# cyberlamp.net
KiCad netlist of a schematic drawn in Altium Designer
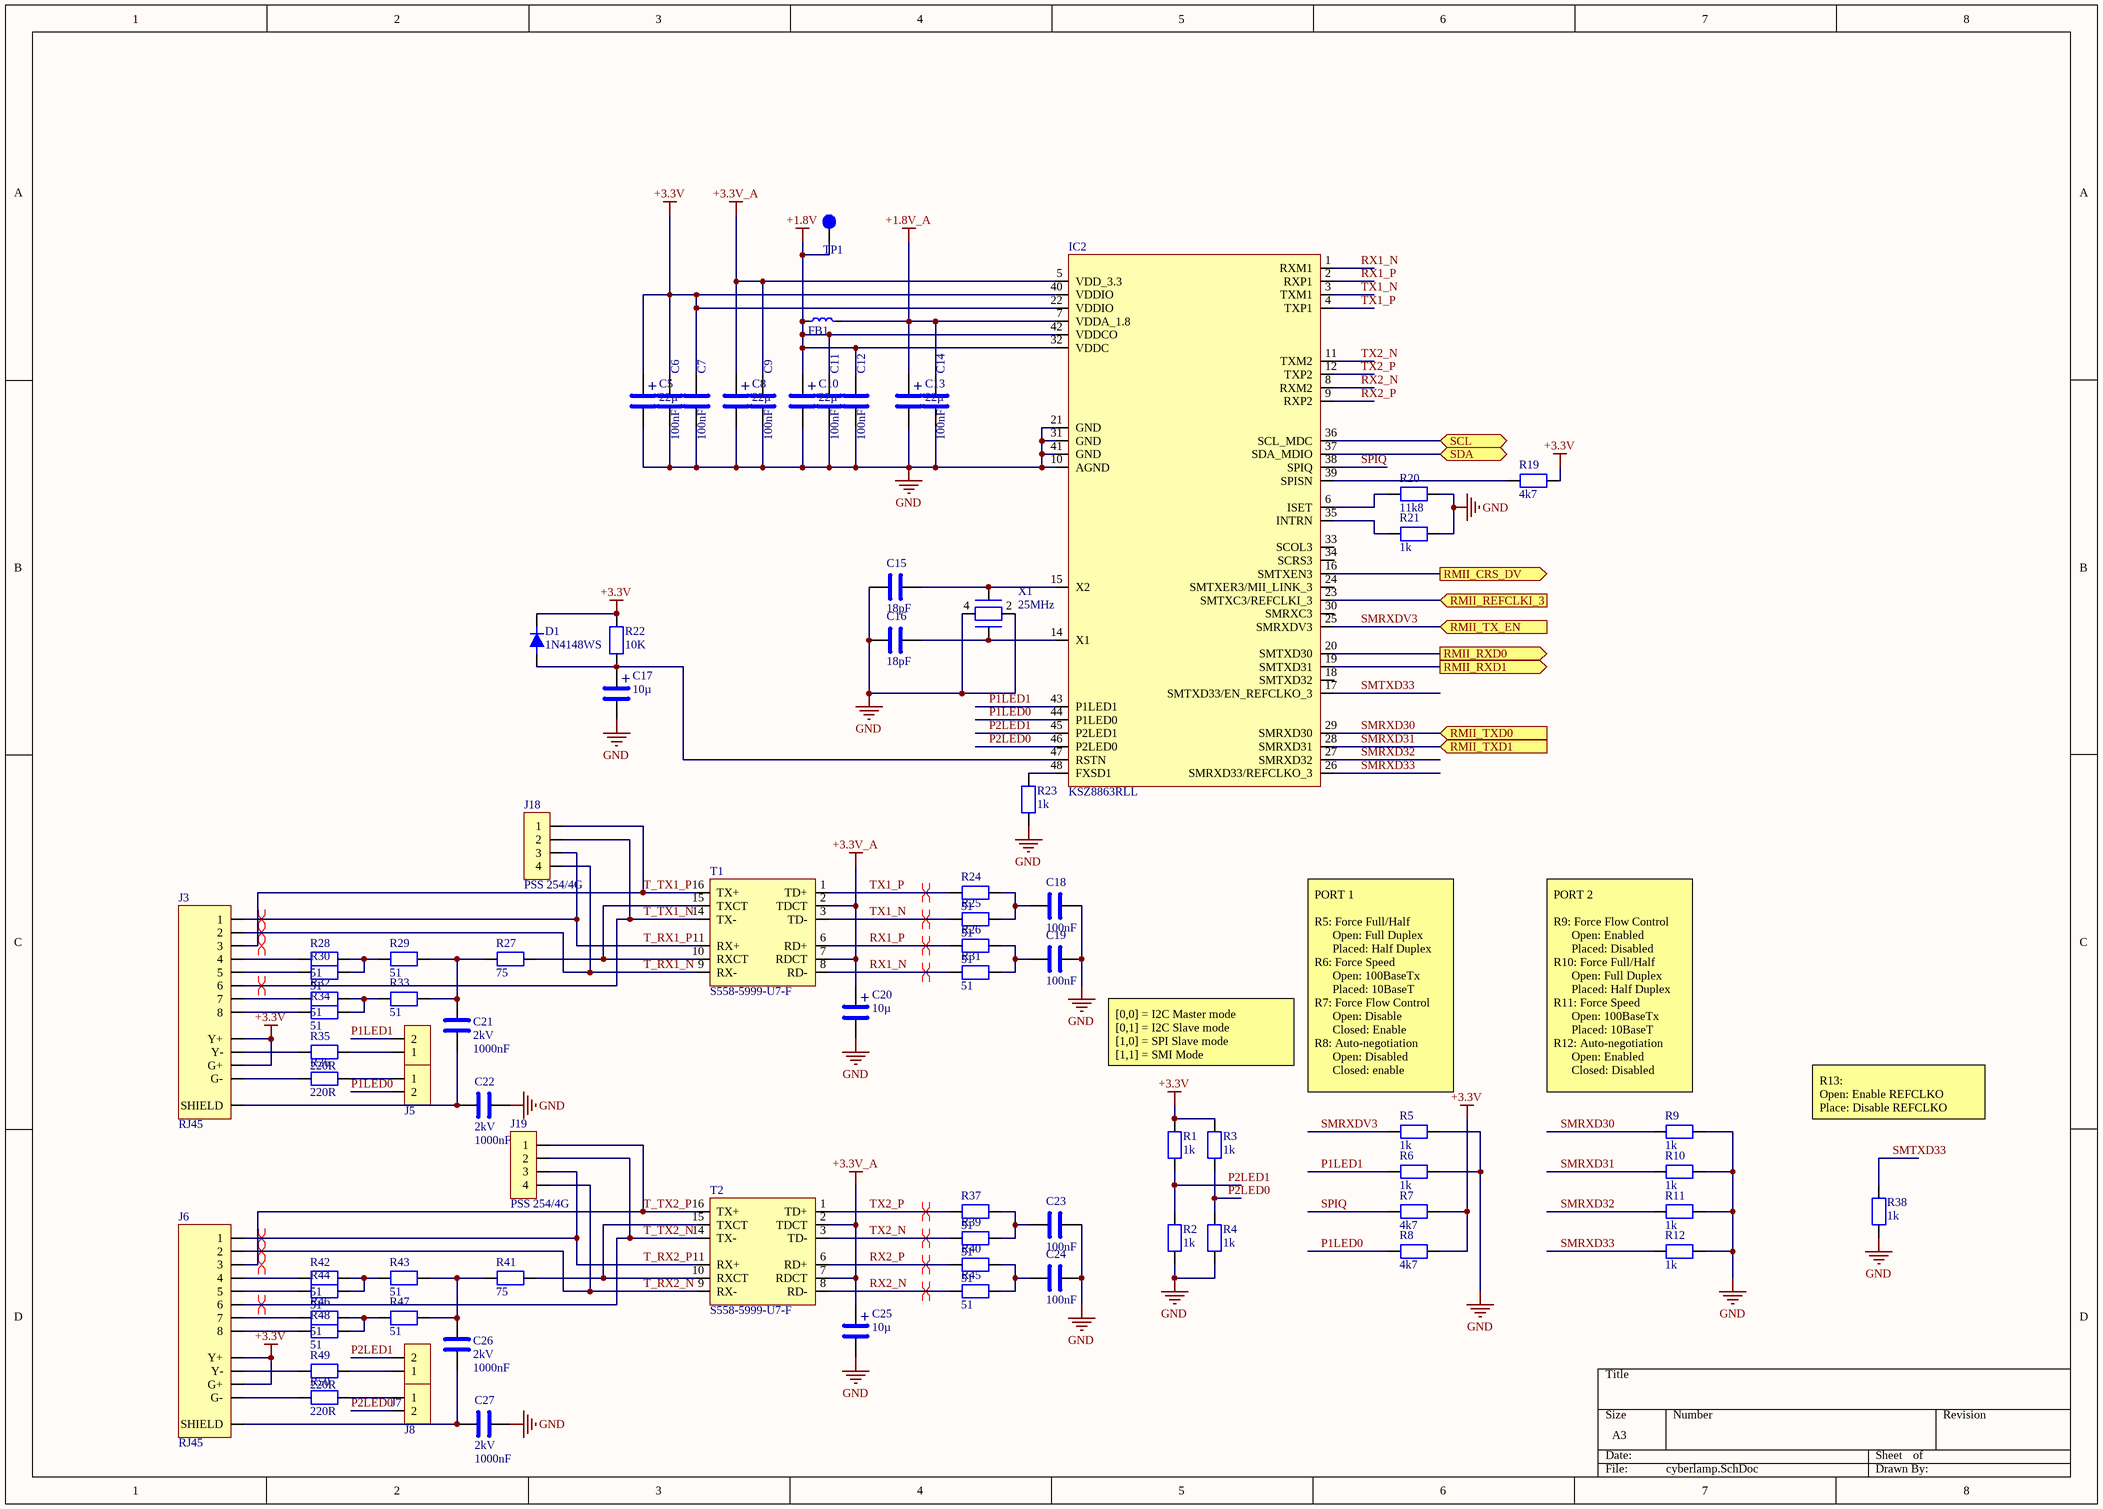
[diagram p0: cyberlamp.SchDoc]

(export (version "E")
  (design (tool "Eeschema 10.0.6"))
  (components
    (comp (ref "C5")
      (value "22µ")
      (footprint "WCAP-ASLU")
      (fields (field (name "VOLTAGE") "6.3V") (field (name "Comment") "Elko 22µF 6.3V WE"))
      (libsource (lib "elko") (part "Elko 22µF 6.3V WE"))
    )
    (comp (ref "C6")
      (value "100nF")
      (footprint "0603")
      (description "100nF 50V MLCC 0603")
      (fields (field (name "VOLTAGE") "50V"))
      (libsource (lib "capacitors") (part "100nF 50V MLCC 0603"))
    )
    (comp (ref "C7")
      (value "100nF")
      (footprint "0603")
      (description "100nF 50V MLCC 0603")
      (fields (field (name "VOLTAGE") "50V"))
      (libsource (lib "capacitors") (part "100nF 50V MLCC 0603"))
    )
    (comp (ref "C8")
      (value "22µ")
      (footprint "WCAP-ASLU")
      (fields (field (name "VOLTAGE") "6.3V") (field (name "Comment") "Elko 22µF 6.3V WE"))
      (libsource (lib "elko") (part "Elko 22µF 6.3V WE"))
    )
    (comp (ref "C9")
      (value "100nF")
      (footprint "0603")
      (description "100nF 50V MLCC 0603")
      (fields (field (name "VOLTAGE") "50V"))
      (libsource (lib "capacitors") (part "100nF 50V MLCC 0603"))
    )
    (comp (ref "C10")
      (value "22µ")
      (footprint "WCAP-ASLU")
      (fields (field (name "VOLTAGE") "6.3V") (field (name "Comment") "Elko 22µF 6.3V WE"))
      (libsource (lib "elko") (part "Elko 22µF 6.3V WE"))
    )
    (comp (ref "C11")
      (value "100nF")
      (footprint "0603")
      (description "100nF 50V MLCC 0603")
      (fields (field (name "VOLTAGE") "50V"))
      (libsource (lib "capacitors") (part "100nF 50V MLCC 0603"))
    )
    (comp (ref "C12")
      (value "100nF")
      (footprint "0603")
      (description "100nF 50V MLCC 0603")
      (fields (field (name "VOLTAGE") "50V"))
      (libsource (lib "capacitors") (part "100nF 50V MLCC 0603"))
    )
    (comp (ref "C13")
      (value "22µ")
      (footprint "WCAP-ASLU")
      (fields (field (name "VOLTAGE") "6.3V") (field (name "Comment") "Elko 22µF 6.3V WE"))
      (libsource (lib "elko") (part "Elko 22µF 6.3V WE"))
    )
    (comp (ref "C14")
      (value "100nF")
      (footprint "0603")
      (description "100nF 50V MLCC 0603")
      (fields (field (name "VOLTAGE") "50V"))
      (libsource (lib "capacitors") (part "100nF 50V MLCC 0603"))
    )
    (comp (ref "C15")
      (value "18pF")
      (footprint "0603")
      (description "18pF 50V MLCC 0603")
      (fields (field (name "VOLTAGE") "50V"))
      (libsource (lib "capacitors") (part "18pF 50V MLCC 0603"))
    )
    (comp (ref "C16")
      (value "18pF")
      (footprint "0603")
      (description "18pF 50V MLCC 0603")
      (fields (field (name "VOLTAGE") "50V"))
      (libsource (lib "capacitors") (part "18pF 50V MLCC 0603"))
    )
    (comp (ref "C17")
      (value "10µ")
      (footprint "Panasonic_b")
      (fields (field (name "VOLTAGE") "16V") (field (name "Comment") "Elko_10uF_16V_PanasonicB"))
      (libsource (lib "elkos") (part "Elko_10uF_16V_PanasonicB"))
    )
    (comp (ref "C18")
      (value "100nF")
      (footprint "0603")
      (description "100nF 50V MLCC 0603")
      (fields (field (name "VOLTAGE") "50V"))
      (libsource (lib "capacitors") (part "100nF 50V MLCC 0603"))
    )
    (comp (ref "C19")
      (value "100nF")
      (footprint "0603")
      (description "100nF 50V MLCC 0603")
      (fields (field (name "VOLTAGE") "50V"))
      (libsource (lib "capacitors") (part "100nF 50V MLCC 0603"))
    )
    (comp (ref "C20")
      (value "10µ")
      (footprint "Panasonic_b")
      (fields (field (name "VOLTAGE") "16V") (field (name "Comment") "Elko_10uF_16V_PanasonicB"))
      (libsource (lib "elkos") (part "Elko_10uF_16V_PanasonicB"))
    )
    (comp (ref "C21")
      (value "1000nF")
      (footprint "1206")
      (description "1000nF 2kV X7R 1206")
      (fields (field (name "VOLTAGE") "2kV") (field (name "Comment") "NP0"))
      (libsource (lib "capacitors") (part "1000nF 2kV X7R 1206"))
    )
    (comp (ref "C22")
      (value "1000nF")
      (footprint "1206")
      (description "1000nF 2kV X7R 1206")
      (fields (field (name "VOLTAGE") "2kV") (field (name "Comment") "NP0"))
      (libsource (lib "capacitors") (part "1000nF 2kV X7R 1206"))
    )
    (comp (ref "C23")
      (value "100nF")
      (footprint "0603")
      (description "100nF 50V MLCC 0603")
      (fields (field (name "VOLTAGE") "50V"))
      (libsource (lib "capacitors") (part "100nF 50V MLCC 0603"))
    )
    (comp (ref "C24")
      (value "100nF")
      (footprint "0603")
      (description "100nF 50V MLCC 0603")
      (fields (field (name "VOLTAGE") "50V"))
      (libsource (lib "capacitors") (part "100nF 50V MLCC 0603"))
    )
    (comp (ref "C25")
      (value "10µ")
      (footprint "Panasonic_b")
      (fields (field (name "VOLTAGE") "16V") (field (name "Comment") "Elko_10uF_16V_PanasonicB"))
      (libsource (lib "elkos") (part "Elko_10uF_16V_PanasonicB"))
    )
    (comp (ref "C26")
      (value "1000nF")
      (footprint "1206")
      (description "1000nF 2kV X7R 1206")
      (fields (field (name "VOLTAGE") "2kV") (field (name "Comment") "NP0"))
      (libsource (lib "capacitors") (part "1000nF 2kV X7R 1206"))
    )
    (comp (ref "C27")
      (value "1000nF")
      (footprint "1206")
      (description "1000nF 2kV X7R 1206")
      (fields (field (name "VOLTAGE") "2kV") (field (name "Comment") "NP0"))
      (libsource (lib "capacitors") (part "1000nF 2kV X7R 1206"))
    )
    (comp (ref "D1")
      (value "1N4148WS")
      (footprint "SOD323")
      (description "Small signal diode")
      (libsource (lib "diodes") (part "1N4148WS"))
    )
    (comp (ref "FB1")
      (value "HI1206N101R-10")
      (footprint "1206")
      (description "3A ferrit bead")
      (libsource (lib "inductors") (part "HI1206N101R-10"))
    )
    (comp (ref "IC2")
      (value "KSZ8863RLL")
      (footprint "LQFP48")
      (description "Dual port ethernet switch with RMII")
      (libsource (lib "misc") (part "KSZ8863RLL"))
    )
    (comp (ref "J3")
      (value "RJ45")
      (footprint "MTJ-88ARX1-FSM-PG-LH")
      (description "RJ45, shielded with LED")
      (libsource (lib "connectors_pc") (part "MTJ-88ARX1-FSM-PG-LH"))
    )
    (comp (ref "J4")
      (value "SL 1X2G 2,54")
      (footprint "SL_1x2 2.54mm")
      (description "Stiftleiste 2pol 2.54mm")
      (libsource (lib "connectors_sl") (part "SL 1X2G 2,54"))
    )
    (comp (ref "J5")
      (value "SL 1X2G 2,54")
      (footprint "SL_1x2 2.54mm")
      (description "Stiftleiste 2pol 2.54mm")
      (libsource (lib "") (part "SL 1X2G 2,54_1"))
    )
    (comp (ref "J6")
      (value "RJ45")
      (footprint "MTJ-88ARX1-FSM-PG-LH")
      (description "RJ45, shielded with LED")
      (libsource (lib "connectors_pc") (part "MTJ-88ARX1-FSM-PG-LH"))
    )
    (comp (ref "J7")
      (value "SL 1X2G 2,54")
      (footprint "SL_1x2 2.54mm")
      (description "Stiftleiste 2pol 2.54mm")
      (libsource (lib "connectors_sl") (part "SL 1X2G 2,54"))
    )
    (comp (ref "J8")
      (value "SL 1X2G 2,54")
      (footprint "SL_1x2 2.54mm")
      (description "Stiftleiste 2pol 2.54mm")
      (libsource (lib "") (part "SL 1X2G 2,54_1"))
    )
    (comp (ref "J18")
      (value "PSS 254/4G")
      (footprint "PSS 4pol")
      (description "PSS 4pol wire-to-board-connector")
      (libsource (lib "connectors_pss") (part "PSS 254/4G"))
    )
    (comp (ref "J19")
      (value "PSS 254/4G")
      (footprint "PSS 4pol")
      (description "PSS 4pol wire-to-board-connector")
      (libsource (lib "connectors_pss") (part "PSS 254/4G"))
    )
    (comp (ref "R1")
      (value "1k")
      (footprint "res0603")
      (description "1k 100mW 0603")
      (fields (field (name "TOLERANCE") "1%"))
      (libsource (lib "resistors0603") (part "1k 100mW 0603"))
    )
    (comp (ref "R2")
      (value "1k")
      (footprint "res0603")
      (description "1k 100mW 0603")
      (fields (field (name "TOLERANCE") "1%"))
      (libsource (lib "resistors0603") (part "1k 100mW 0603"))
    )
    (comp (ref "R3")
      (value "1k")
      (footprint "res0603")
      (description "1k 100mW 0603")
      (fields (field (name "TOLERANCE") "1%"))
      (libsource (lib "resistors0603") (part "1k 100mW 0603"))
    )
    (comp (ref "R4")
      (value "1k")
      (footprint "res0603")
      (description "1k 100mW 0603")
      (fields (field (name "TOLERANCE") "1%"))
      (libsource (lib "resistors0603") (part "1k 100mW 0603"))
    )
    (comp (ref "R5")
      (value "1k")
      (footprint "res0603")
      (description "1k 100mW 0603")
      (fields (field (name "TOLERANCE") "1%"))
      (libsource (lib "resistors0603") (part "1k 100mW 0603"))
    )
    (comp (ref "R6")
      (value "1k")
      (footprint "res0603")
      (description "1k 100mW 0603")
      (fields (field (name "TOLERANCE") "1%"))
      (libsource (lib "resistors0603") (part "1k 100mW 0603"))
    )
    (comp (ref "R7")
      (value "4k7")
      (footprint "res0603")
      (description "4k7 100mW 0603")
      (libsource (lib "resistors") (part "4k7 100mW 0603"))
    )
    (comp (ref "R8")
      (value "4k7")
      (footprint "res0603")
      (description "4k7 100mW 0603")
      (libsource (lib "resistors") (part "4k7 100mW 0603"))
    )
    (comp (ref "R9")
      (value "1k")
      (footprint "res0603")
      (description "1k 100mW 0603")
      (fields (field (name "TOLERANCE") "1%"))
      (libsource (lib "resistors0603") (part "1k 100mW 0603"))
    )
    (comp (ref "R10")
      (value "1k")
      (footprint "res0603")
      (description "1k 100mW 0603")
      (fields (field (name "TOLERANCE") "1%"))
      (libsource (lib "resistors0603") (part "1k 100mW 0603"))
    )
    (comp (ref "R11")
      (value "1k")
      (footprint "res0603")
      (description "1k 100mW 0603")
      (fields (field (name "TOLERANCE") "1%"))
      (libsource (lib "resistors0603") (part "1k 100mW 0603"))
    )
    (comp (ref "R12")
      (value "1k")
      (footprint "res0603")
      (description "1k 100mW 0603")
      (fields (field (name "TOLERANCE") "1%"))
      (libsource (lib "resistors0603") (part "1k 100mW 0603"))
    )
    (comp (ref "R19")
      (value "4k7")
      (footprint "res0603")
      (description "4k7 100mW 0603")
      (libsource (lib "resistors") (part "4k7 100mW 0603"))
    )
    (comp (ref "R20")
      (value "11k8")
      (footprint "res0603")
      (description "11k8 100mW 0603")
      (fields (field (name "TOLERANCE") "1%"))
      (libsource (lib "resistors0603") (part "11k8 100mW 0603"))
    )
    (comp (ref "R21")
      (value "1k")
      (footprint "res0603")
      (description "1k 100mW 0603")
      (fields (field (name "TOLERANCE") "1%"))
      (libsource (lib "resistors0603") (part "1k 100mW 0603"))
    )
    (comp (ref "R22")
      (value "10K")
      (footprint "res0603")
      (description "10K 100mW 0603")
      (fields (field (name "TOLERANCE") "1%"))
      (libsource (lib "resistors") (part "10K 100mW 0603"))
    )
    (comp (ref "R23")
      (value "1k")
      (footprint "res0603")
      (description "1k 100mW 0603")
      (fields (field (name "TOLERANCE") "1%"))
      (libsource (lib "resistors0603") (part "1k 100mW 0603"))
    )
    (comp (ref "R24")
      (value "51")
      (footprint "res0603")
      (description "51 100mW 0603")
      (fields (field (name "TOLERANCE") "5%") (field (name "Comment") "51R 100mW 0603"))
      (libsource (lib "resistors0603") (part "51R 100mW 0603"))
    )
    (comp (ref "R25")
      (value "51")
      (footprint "res0603")
      (description "51 100mW 0603")
      (fields (field (name "TOLERANCE") "5%") (field (name "Comment") "51R 100mW 0603"))
      (libsource (lib "resistors0603") (part "51R 100mW 0603"))
    )
    (comp (ref "R26")
      (value "51")
      (footprint "res0603")
      (description "51 100mW 0603")
      (fields (field (name "TOLERANCE") "5%") (field (name "Comment") "51R 100mW 0603"))
      (libsource (lib "resistors0603") (part "51R 100mW 0603"))
    )
    (comp (ref "R27")
      (value "75")
      (footprint "res0603")
      (description "75 100mW 0603")
      (fields (field (name "TOLERANCE") "1%") (field (name "Comment") "75R 100mW 0603"))
      (libsource (lib "resistors0603") (part "75R 100mW 0603"))
    )
    (comp (ref "R28")
      (value "51")
      (footprint "res0603")
      (description "51 100mW 0603")
      (fields (field (name "TOLERANCE") "5%") (field (name "Comment") "51R 100mW 0603"))
      (libsource (lib "resistors0603") (part "51R 100mW 0603"))
    )
    (comp (ref "R29")
      (value "51")
      (footprint "res0603")
      (description "51 100mW 0603")
      (fields (field (name "TOLERANCE") "5%") (field (name "Comment") "51R 100mW 0603"))
      (libsource (lib "resistors0603") (part "51R 100mW 0603"))
    )
    (comp (ref "R30")
      (value "51")
      (footprint "res0603")
      (description "51 100mW 0603")
      (fields (field (name "TOLERANCE") "5%") (field (name "Comment") "51R 100mW 0603"))
      (libsource (lib "resistors0603") (part "51R 100mW 0603"))
    )
    (comp (ref "R31")
      (value "51")
      (footprint "res0603")
      (description "51 100mW 0603")
      (fields (field (name "TOLERANCE") "5%") (field (name "Comment") "51R 100mW 0603"))
      (libsource (lib "resistors0603") (part "51R 100mW 0603"))
    )
    (comp (ref "R32")
      (value "51")
      (footprint "res0603")
      (description "51 100mW 0603")
      (fields (field (name "TOLERANCE") "5%") (field (name "Comment") "51R 100mW 0603"))
      (libsource (lib "resistors0603") (part "51R 100mW 0603"))
    )
    (comp (ref "R33")
      (value "51")
      (footprint "res0603")
      (description "51 100mW 0603")
      (fields (field (name "TOLERANCE") "5%") (field (name "Comment") "51R 100mW 0603"))
      (libsource (lib "resistors0603") (part "51R 100mW 0603"))
    )
    (comp (ref "R34")
      (value "51")
      (footprint "res0603")
      (description "51 100mW 0603")
      (fields (field (name "TOLERANCE") "5%") (field (name "Comment") "51R 100mW 0603"))
      (libsource (lib "resistors0603") (part "51R 100mW 0603"))
    )
    (comp (ref "R35")
      (value "220R")
      (footprint "res0603")
      (description "220R 100mW 0603")
      (fields (field (name "TOLERANCE") "1%"))
      (libsource (lib "resistors0603") (part "220R 100mW 0603"))
    )
    (comp (ref "R36")
      (value "220R")
      (footprint "res0603")
      (description "220R 100mW 0603")
      (fields (field (name "TOLERANCE") "1%"))
      (libsource (lib "resistors0603") (part "220R 100mW 0603"))
    )
    (comp (ref "R37")
      (value "51")
      (footprint "res0603")
      (description "51 100mW 0603")
      (fields (field (name "TOLERANCE") "5%") (field (name "Comment") "51R 100mW 0603"))
      (libsource (lib "resistors0603") (part "51R 100mW 0603"))
    )
    (comp (ref "R38")
      (value "1k")
      (footprint "res0603")
      (description "1k 100mW 0603")
      (fields (field (name "TOLERANCE") "1%"))
      (libsource (lib "resistors0603") (part "1k 100mW 0603"))
    )
    (comp (ref "R39")
      (value "51")
      (footprint "res0603")
      (description "51 100mW 0603")
      (fields (field (name "TOLERANCE") "5%") (field (name "Comment") "51R 100mW 0603"))
      (libsource (lib "resistors0603") (part "51R 100mW 0603"))
    )
    (comp (ref "R40")
      (value "51")
      (footprint "res0603")
      (description "51 100mW 0603")
      (fields (field (name "TOLERANCE") "5%") (field (name "Comment") "51R 100mW 0603"))
      (libsource (lib "resistors0603") (part "51R 100mW 0603"))
    )
    (comp (ref "R41")
      (value "75")
      (footprint "res0603")
      (description "75 100mW 0603")
      (fields (field (name "TOLERANCE") "1%") (field (name "Comment") "75R 100mW 0603"))
      (libsource (lib "resistors0603") (part "75R 100mW 0603"))
    )
    (comp (ref "R42")
      (value "51")
      (footprint "res0603")
      (description "51 100mW 0603")
      (fields (field (name "TOLERANCE") "5%") (field (name "Comment") "51R 100mW 0603"))
      (libsource (lib "resistors0603") (part "51R 100mW 0603"))
    )
    (comp (ref "R43")
      (value "51")
      (footprint "res0603")
      (description "51 100mW 0603")
      (fields (field (name "TOLERANCE") "5%") (field (name "Comment") "51R 100mW 0603"))
      (libsource (lib "resistors0603") (part "51R 100mW 0603"))
    )
    (comp (ref "R44")
      (value "51")
      (footprint "res0603")
      (description "51 100mW 0603")
      (fields (field (name "TOLERANCE") "5%") (field (name "Comment") "51R 100mW 0603"))
      (libsource (lib "resistors0603") (part "51R 100mW 0603"))
    )
    (comp (ref "R45")
      (value "51")
      (footprint "res0603")
      (description "51 100mW 0603")
      (fields (field (name "TOLERANCE") "5%") (field (name "Comment") "51R 100mW 0603"))
      (libsource (lib "resistors0603") (part "51R 100mW 0603"))
    )
    (comp (ref "R46")
      (value "51")
      (footprint "res0603")
      (description "51 100mW 0603")
      (fields (field (name "TOLERANCE") "5%") (field (name "Comment") "51R 100mW 0603"))
      (libsource (lib "resistors0603") (part "51R 100mW 0603"))
    )
    (comp (ref "R47")
      (value "51")
      (footprint "res0603")
      (description "51 100mW 0603")
      (fields (field (name "TOLERANCE") "5%") (field (name "Comment") "51R 100mW 0603"))
      (libsource (lib "resistors0603") (part "51R 100mW 0603"))
    )
    (comp (ref "R48")
      (value "51")
      (footprint "res0603")
      (description "51 100mW 0603")
      (fields (field (name "TOLERANCE") "5%") (field (name "Comment") "51R 100mW 0603"))
      (libsource (lib "resistors0603") (part "51R 100mW 0603"))
    )
    (comp (ref "R49")
      (value "220R")
      (footprint "res0603")
      (description "220R 100mW 0603")
      (fields (field (name "TOLERANCE") "1%"))
      (libsource (lib "resistors0603") (part "220R 100mW 0603"))
    )
    (comp (ref "R50")
      (value "220R")
      (footprint "res0603")
      (description "220R 100mW 0603")
      (fields (field (name "TOLERANCE") "1%"))
      (libsource (lib "resistors0603") (part "220R 100mW 0603"))
    )
    (comp (ref "T1")
      (value "S558-5999-U7-F")
      (footprint "S558-5999-U7-F")
      (description "Ethernet transformer")
      (libsource (lib "inductors2") (part "S558-5999-U7-F"))
    )
    (comp (ref "T2")
      (value "S558-5999-U7-F")
      (footprint "S558-5999-U7-F")
      (description "Ethernet transformer")
      (libsource (lib "inductors2") (part "S558-5999-U7-F"))
    )
    (comp (ref "TP1") (value "testpoint") (footprint "testpoint") (libsource (lib "misc") (part "testpoint")))
    (comp (ref "X1")
      (value "25MHz")
      (footprint "ABM8")
      (description "ABM8 25MHz crystal")
      (libsource (lib "crystals") (part "ABM8-25.000MHZ-B2-T"))
    )
  )
  (nets
    (net (code "1") (name "+1.8V") (class "Default")
      (node (ref "C10") (pin "+") (pinfunction "+_+") (pintype "passive"))
      (node (ref "C11") (pin "1") (pinfunction "1_1") (pintype "passive"))
      (node (ref "C12") (pin "1") (pinfunction "1_1") (pintype "passive"))
      (node (ref "FB1") (pin "1") (pinfunction "1_1") (pintype "passive"))
      (node (ref "IC2") (pin "32") (pinfunction "VDDC_32") (pintype "passive"))
      (node (ref "IC2") (pin "42") (pinfunction "VDDCO_42") (pintype "passive"))
      (node (ref "TP1") (pin "1") (pinfunction "1_1") (pintype "passive"))
    )
    (net (code "2") (name "+1.8V_A") (class "Default")
      (node (ref "C13") (pin "+") (pinfunction "+_+") (pintype "passive"))
      (node (ref "C14") (pin "1") (pinfunction "1_1") (pintype "passive"))
      (node (ref "FB1") (pin "2") (pinfunction "2_2") (pintype "passive"))
      (node (ref "IC2") (pin "7") (pinfunction "VDDA_1.8_7") (pintype "passive"))
    )
    (net (code "3") (name "+3.3V") (class "Default")
      (node (ref "C5") (pin "+") (pinfunction "+_+") (pintype "passive"))
      (node (ref "C6") (pin "1") (pinfunction "1_1") (pintype "passive"))
      (node (ref "C7") (pin "1") (pinfunction "1_1") (pintype "passive"))
      (node (ref "D1") (pin "1") (pinfunction "1_1") (pintype "passive"))
      (node (ref "IC2") (pin "22") (pinfunction "VDDIO_22") (pintype "passive"))
      (node (ref "IC2") (pin "40") (pinfunction "VDDIO_40") (pintype "passive"))
      (node (ref "J3") (pin "10") (pinfunction "Y+_10") (pintype "passive"))
      (node (ref "J3") (pin "12") (pinfunction "G+_12") (pintype "passive"))
      (node (ref "J6") (pin "10") (pinfunction "Y+_10") (pintype "passive"))
      (node (ref "J6") (pin "12") (pinfunction "G+_12") (pintype "passive"))
      (node (ref "R1") (pin "2") (pinfunction "2_2") (pintype "passive"))
      (node (ref "R19") (pin "1") (pinfunction "1_1") (pintype "passive"))
      (node (ref "R22") (pin "2") (pinfunction "2_2") (pintype "passive"))
      (node (ref "R3") (pin "2") (pinfunction "2_2") (pintype "passive"))
      (node (ref "R7") (pin "1") (pinfunction "1_1") (pintype "passive"))
      (node (ref "R8") (pin "1") (pinfunction "1_1") (pintype "passive"))
    )
    (net (code "4") (name "+3.3V_A") (class "Default")
      (node (ref "C20") (pin "+") (pinfunction "+_+") (pintype "passive"))
      (node (ref "C25") (pin "+") (pinfunction "+_+") (pintype "passive"))
      (node (ref "C8") (pin "+") (pinfunction "+_+") (pintype "passive"))
      (node (ref "C9") (pin "1") (pinfunction "1_1") (pintype "passive"))
      (node (ref "IC2") (pin "5") (pinfunction "VDD_3.3_5") (pintype "passive"))
      (node (ref "T1") (pin "2") (pinfunction "TDCT_2") (pintype "passive"))
      (node (ref "T1") (pin "7") (pinfunction "RDCT_7") (pintype "passive"))
      (node (ref "T2") (pin "2") (pinfunction "TDCT_2") (pintype "passive"))
      (node (ref "T2") (pin "7") (pinfunction "RDCT_7") (pintype "passive"))
    )
    (net (code "5") (name "/P1LED0") (class "Default")
      (node (ref "IC2") (pin "44") (pinfunction "P1LED0_44") (pintype "passive"))
      (node (ref "J5") (pin "2") (pinfunction "2_2") (pintype "passive"))
      (node (ref "R8") (pin "2") (pinfunction "2_2") (pintype "passive"))
    )
    (net (code "6") (name "/P1LED1") (class "Default")
      (node (ref "IC2") (pin "43") (pinfunction "P1LED1_43") (pintype "passive"))
      (node (ref "J4") (pin "2") (pinfunction "2_2") (pintype "passive"))
      (node (ref "R6") (pin "2") (pinfunction "2_2") (pintype "passive"))
    )
    (net (code "7") (name "/P2LED0") (class "Default")
      (node (ref "IC2") (pin "46") (pinfunction "P2LED0_46") (pintype "passive"))
      (node (ref "J8") (pin "2") (pinfunction "2_2") (pintype "passive"))
      (node (ref "R3") (pin "1") (pinfunction "1_1") (pintype "passive"))
      (node (ref "R4") (pin "2") (pinfunction "2_2") (pintype "passive"))
    )
    (net (code "8") (name "/P2LED1") (class "Default")
      (node (ref "IC2") (pin "45") (pinfunction "P2LED1_45") (pintype "passive"))
      (node (ref "J7") (pin "2") (pinfunction "2_2") (pintype "passive"))
      (node (ref "R1") (pin "1") (pinfunction "1_1") (pintype "passive"))
      (node (ref "R2") (pin "2") (pinfunction "2_2") (pintype "passive"))
    )
    (net (code "9") (name "/RMII_CRS_DV") (class "Default")
      (node (ref "IC2") (pin "16") (pinfunction "SMTXEN3_16") (pintype "passive"))
    )
    (net (code "10") (name "/RMII_REFCLKI_3") (class "Default")
      (node (ref "IC2") (pin "23") (pinfunction "SMTXC3/REFCLKI_3_23") (pintype "passive"))
    )
    (net (code "11") (name "/RMII_RXD0") (class "Default")
      (node (ref "IC2") (pin "20") (pinfunction "SMTXD30_20") (pintype "passive"))
    )
    (net (code "12") (name "/RMII_RXD1") (class "Default")
      (node (ref "IC2") (pin "19") (pinfunction "SMTXD31_19") (pintype "passive"))
    )
    (net (code "13") (name "/RX1_N") (class "Default")
      (node (ref "IC2") (pin "1") (pinfunction "RXM1_1") (pintype "passive"))
      (node (ref "R31") (pin "2") (pinfunction "2_2") (pintype "passive"))
      (node (ref "T1") (pin "8") (pinfunction "RD-_8") (pintype "passive"))
    )
    (net (code "14") (name "/RX1_P") (class "Default")
      (node (ref "IC2") (pin "2") (pinfunction "RXP1_2") (pintype "passive"))
      (node (ref "R26") (pin "2") (pinfunction "2_2") (pintype "passive"))
      (node (ref "T1") (pin "6") (pinfunction "RD+_6") (pintype "passive"))
    )
    (net (code "15") (name "/RX2_N") (class "Default")
      (node (ref "IC2") (pin "8") (pinfunction "RXM2_8") (pintype "passive"))
      (node (ref "R45") (pin "2") (pinfunction "2_2") (pintype "passive"))
      (node (ref "T2") (pin "8") (pinfunction "RD-_8") (pintype "passive"))
    )
    (net (code "16") (name "/RX2_P") (class "Default")
      (node (ref "IC2") (pin "9") (pinfunction "RXP2_9") (pintype "passive"))
      (node (ref "R40") (pin "2") (pinfunction "2_2") (pintype "passive"))
      (node (ref "T2") (pin "6") (pinfunction "RD+_6") (pintype "passive"))
    )
    (net (code "17") (name "/SCL") (class "Default")
      (node (ref "IC2") (pin "36") (pinfunction "SCL_MDC_36") (pintype "passive"))
    )
    (net (code "18") (name "/SDA") (class "Default")
      (node (ref "IC2") (pin "37") (pinfunction "SDA_MDIO_37") (pintype "passive"))
    )
    (net (code "19") (name "/SMRXD30") (class "Default")
      (node (ref "IC2") (pin "29") (pinfunction "SMRXD30_29") (pintype "passive"))
      (node (ref "R9") (pin "2") (pinfunction "2_2") (pintype "passive"))
    )
    (net (code "20") (name "/SMRXD31") (class "Default")
      (node (ref "IC2") (pin "28") (pinfunction "SMRXD31_28") (pintype "passive"))
      (node (ref "R10") (pin "2") (pinfunction "2_2") (pintype "passive"))
    )
    (net (code "21") (name "/SMRXD32") (class "Default")
      (node (ref "IC2") (pin "27") (pinfunction "SMRXD32_27") (pintype "passive"))
      (node (ref "R11") (pin "2") (pinfunction "2_2") (pintype "passive"))
    )
    (net (code "22") (name "/SMRXD33") (class "Default")
      (node (ref "IC2") (pin "26") (pinfunction "SMRXD33/REFCLKO_3_26") (pintype "passive"))
      (node (ref "R12") (pin "2") (pinfunction "2_2") (pintype "passive"))
    )
    (net (code "23") (name "/SMRXDV3") (class "Default")
      (node (ref "IC2") (pin "25") (pinfunction "SMRXDV3_25") (pintype "passive"))
      (node (ref "R5") (pin "2") (pinfunction "2_2") (pintype "passive"))
    )
    (net (code "24") (name "/SMTXD33") (class "Default")
      (node (ref "IC2") (pin "17") (pinfunction "SMTXD33/EN_REFCLKO_3_17") (pintype "passive"))
      (node (ref "R38") (pin "1") (pinfunction "1_1") (pintype "passive"))
    )
    (net (code "25") (name "/SPIQ") (class "Default")
      (node (ref "IC2") (pin "38") (pinfunction "SPIQ_38") (pintype "passive"))
      (node (ref "R7") (pin "2") (pinfunction "2_2") (pintype "passive"))
    )
    (net (code "26") (name "/TX1_N") (class "Default")
      (node (ref "IC2") (pin "3") (pinfunction "TXM1_3") (pintype "passive"))
      (node (ref "R25") (pin "2") (pinfunction "2_2") (pintype "passive"))
      (node (ref "T1") (pin "3") (pinfunction "TD-_3") (pintype "passive"))
    )
    (net (code "27") (name "/TX1_P") (class "Default")
      (node (ref "IC2") (pin "4") (pinfunction "TXP1_4") (pintype "passive"))
      (node (ref "R24") (pin "2") (pinfunction "2_2") (pintype "passive"))
      (node (ref "T1") (pin "1") (pinfunction "TD+_1") (pintype "passive"))
    )
    (net (code "28") (name "/TX2_N") (class "Default")
      (node (ref "IC2") (pin "11") (pinfunction "TXM2_11") (pintype "passive"))
      (node (ref "R39") (pin "2") (pinfunction "2_2") (pintype "passive"))
      (node (ref "T2") (pin "3") (pinfunction "TD-_3") (pintype "passive"))
    )
    (net (code "29") (name "/TX2_P") (class "Default")
      (node (ref "IC2") (pin "12") (pinfunction "TXP2_12") (pintype "passive"))
      (node (ref "R37") (pin "2") (pinfunction "2_2") (pintype "passive"))
      (node (ref "T2") (pin "1") (pinfunction "TD+_1") (pintype "passive"))
    )
    (net (code "30") (name "/T_RX1_N") (class "Default")
      (node (ref "J18") (pin "4") (pinfunction "4_4") (pintype "passive"))
      (node (ref "J3") (pin "2") (pinfunction "2_2") (pintype "passive"))
      (node (ref "T1") (pin "9") (pinfunction "RX-_9") (pintype "passive"))
    )
    (net (code "31") (name "/T_RX1_P") (class "Default")
      (node (ref "J18") (pin "3") (pinfunction "3_3") (pintype "passive"))
      (node (ref "J3") (pin "1") (pinfunction "1_1") (pintype "passive"))
      (node (ref "T1") (pin "11") (pinfunction "RX+_11") (pintype "passive"))
    )
    (net (code "32") (name "/T_RX2_N") (class "Default")
      (node (ref "J19") (pin "4") (pinfunction "4_4") (pintype "passive"))
      (node (ref "J6") (pin "2") (pinfunction "2_2") (pintype "passive"))
      (node (ref "T2") (pin "9") (pinfunction "RX-_9") (pintype "passive"))
    )
    (net (code "33") (name "/T_RX2_P") (class "Default")
      (node (ref "J19") (pin "3") (pinfunction "3_3") (pintype "passive"))
      (node (ref "J6") (pin "1") (pinfunction "1_1") (pintype "passive"))
      (node (ref "T2") (pin "11") (pinfunction "RX+_11") (pintype "passive"))
    )
    (net (code "34") (name "/T_TX1_N") (class "Default")
      (node (ref "J18") (pin "2") (pinfunction "2_2") (pintype "passive"))
      (node (ref "J3") (pin "6") (pinfunction "6_6") (pintype "passive"))
      (node (ref "T1") (pin "14") (pinfunction "TX-_14") (pintype "passive"))
    )
    (net (code "35") (name "/T_TX1_P") (class "Default")
      (node (ref "J18") (pin "1") (pinfunction "1_1") (pintype "passive"))
      (node (ref "J3") (pin "3") (pinfunction "3_3") (pintype "passive"))
      (node (ref "T1") (pin "16") (pinfunction "TX+_16") (pintype "passive"))
    )
    (net (code "36") (name "/T_TX2_N") (class "Default")
      (node (ref "J19") (pin "2") (pinfunction "2_2") (pintype "passive"))
      (node (ref "J6") (pin "6") (pinfunction "6_6") (pintype "passive"))
      (node (ref "T2") (pin "14") (pinfunction "TX-_14") (pintype "passive"))
    )
    (net (code "37") (name "/T_TX2_P") (class "Default")
      (node (ref "J19") (pin "1") (pinfunction "1_1") (pintype "passive"))
      (node (ref "J6") (pin "3") (pinfunction "3_3") (pintype "passive"))
      (node (ref "T2") (pin "16") (pinfunction "TX+_16") (pintype "passive"))
    )
    (net (code "38") (name "GND") (class "Default")
      (node (ref "C10") (pin "-") (pinfunction "-_-") (pintype "passive"))
      (node (ref "C11") (pin "2") (pinfunction "2_2") (pintype "passive"))
      (node (ref "C12") (pin "2") (pinfunction "2_2") (pintype "passive"))
      (node (ref "C13") (pin "-") (pinfunction "-_-") (pintype "passive"))
      (node (ref "C14") (pin "2") (pinfunction "2_2") (pintype "passive"))
      (node (ref "C15") (pin "1") (pinfunction "1_1") (pintype "passive"))
      (node (ref "C16") (pin "1") (pinfunction "1_1") (pintype "passive"))
      (node (ref "C17") (pin "-") (pinfunction "-_-") (pintype "passive"))
      (node (ref "C18") (pin "2") (pinfunction "2_2") (pintype "passive"))
      (node (ref "C19") (pin "2") (pinfunction "2_2") (pintype "passive"))
      (node (ref "C20") (pin "-") (pinfunction "-_-") (pintype "passive"))
      (node (ref "C22") (pin "1") (pinfunction "1_1") (pintype "passive"))
      (node (ref "C23") (pin "2") (pinfunction "2_2") (pintype "passive"))
      (node (ref "C24") (pin "2") (pinfunction "2_2") (pintype "passive"))
      (node (ref "C25") (pin "-") (pinfunction "-_-") (pintype "passive"))
      (node (ref "C27") (pin "1") (pinfunction "1_1") (pintype "passive"))
      (node (ref "C5") (pin "-") (pinfunction "-_-") (pintype "passive"))
      (node (ref "C6") (pin "2") (pinfunction "2_2") (pintype "passive"))
      (node (ref "C7") (pin "2") (pinfunction "2_2") (pintype "passive"))
      (node (ref "C8") (pin "-") (pinfunction "-_-") (pintype "passive"))
      (node (ref "C9") (pin "2") (pinfunction "2_2") (pintype "passive"))
      (node (ref "IC2") (pin "10") (pinfunction "AGND_10") (pintype "passive"))
      (node (ref "IC2") (pin "21") (pinfunction "GND_21") (pintype "passive"))
      (node (ref "IC2") (pin "31") (pinfunction "GND_31") (pintype "passive"))
      (node (ref "IC2") (pin "41") (pinfunction "GND_41") (pintype "passive"))
      (node (ref "R10") (pin "1") (pinfunction "1_1") (pintype "passive"))
      (node (ref "R11") (pin "1") (pinfunction "1_1") (pintype "passive"))
      (node (ref "R12") (pin "1") (pinfunction "1_1") (pintype "passive"))
      (node (ref "R2") (pin "1") (pinfunction "1_1") (pintype "passive"))
      (node (ref "R20") (pin "1") (pinfunction "1_1") (pintype "passive"))
      (node (ref "R21") (pin "1") (pinfunction "1_1") (pintype "passive"))
      (node (ref "R23") (pin "2") (pinfunction "2_2") (pintype "passive"))
      (node (ref "R38") (pin "2") (pinfunction "2_2") (pintype "passive"))
      (node (ref "R4") (pin "1") (pinfunction "1_1") (pintype "passive"))
      (node (ref "R5") (pin "1") (pinfunction "1_1") (pintype "passive"))
      (node (ref "R6") (pin "1") (pinfunction "1_1") (pintype "passive"))
      (node (ref "R9") (pin "1") (pinfunction "1_1") (pintype "passive"))
      (node (ref "X1") (pin "2") (pinfunction "2_2") (pintype "passive"))
      (node (ref "X1") (pin "4") (pinfunction "4_4") (pintype "passive"))
    )
    (net (code "39") (name "Net-(C18-Pad1)") (class "Default")
      (node (ref "C18") (pin "1") (pinfunction "1_1") (pintype "passive"))
      (node (ref "R24") (pin "1") (pinfunction "1_1") (pintype "passive"))
      (node (ref "R25") (pin "1") (pinfunction "1_1") (pintype "passive"))
    )
    (net (code "40") (name "Net-(C19-Pad1)") (class "Default")
      (node (ref "C19") (pin "1") (pinfunction "1_1") (pintype "passive"))
      (node (ref "R26") (pin "1") (pinfunction "1_1") (pintype "passive"))
      (node (ref "R31") (pin "1") (pinfunction "1_1") (pintype "passive"))
    )
    (net (code "41") (name "Net-(C21-Pad2)") (class "Default")
      (node (ref "C21") (pin "2") (pinfunction "2_2") (pintype "passive"))
      (node (ref "R27") (pin "2") (pinfunction "2_2") (pintype "passive"))
      (node (ref "R29") (pin "1") (pinfunction "1_1") (pintype "passive"))
      (node (ref "R33") (pin "1") (pinfunction "1_1") (pintype "passive"))
    )
    (net (code "42") (name "Net-(C23-Pad1)") (class "Default")
      (node (ref "C23") (pin "1") (pinfunction "1_1") (pintype "passive"))
      (node (ref "R37") (pin "1") (pinfunction "1_1") (pintype "passive"))
      (node (ref "R39") (pin "1") (pinfunction "1_1") (pintype "passive"))
    )
    (net (code "43") (name "Net-(C24-Pad1)") (class "Default")
      (node (ref "C24") (pin "1") (pinfunction "1_1") (pintype "passive"))
      (node (ref "R40") (pin "1") (pinfunction "1_1") (pintype "passive"))
      (node (ref "R45") (pin "1") (pinfunction "1_1") (pintype "passive"))
    )
    (net (code "44") (name "Net-(C26-Pad2)") (class "Default")
      (node (ref "C26") (pin "2") (pinfunction "2_2") (pintype "passive"))
      (node (ref "R41") (pin "2") (pinfunction "2_2") (pintype "passive"))
      (node (ref "R43") (pin "1") (pinfunction "1_1") (pintype "passive"))
      (node (ref "R47") (pin "1") (pinfunction "1_1") (pintype "passive"))
    )
    (net (code "45") (name "Net-(IC2-FXSD1)") (class "Default")
      (node (ref "IC2") (pin "48") (pinfunction "FXSD1_48") (pintype "passive"))
      (node (ref "R23") (pin "1") (pinfunction "1_1") (pintype "passive"))
    )
    (net (code "46") (name "Net-(IC2-INTRN)") (class "Default")
      (node (ref "IC2") (pin "35") (pinfunction "INTRN_35") (pintype "passive"))
      (node (ref "R21") (pin "2") (pinfunction "2_2") (pintype "passive"))
    )
    (net (code "47") (name "Net-(IC2-ISET)") (class "Default")
      (node (ref "IC2") (pin "6") (pinfunction "ISET_6") (pintype "passive"))
      (node (ref "R20") (pin "2") (pinfunction "2_2") (pintype "passive"))
    )
    (net (code "48") (name "Net-(IC2-RSTN)") (class "Default")
      (node (ref "C17") (pin "+") (pinfunction "+_+") (pintype "passive"))
      (node (ref "D1") (pin "2") (pinfunction "2_2") (pintype "passive"))
      (node (ref "IC2") (pin "47") (pinfunction "RSTN_47") (pintype "passive"))
      (node (ref "R22") (pin "1") (pinfunction "1_1") (pintype "passive"))
    )
    (net (code "49") (name "Net-(IC2-SPISN)") (class "Default")
      (node (ref "IC2") (pin "39") (pinfunction "SPISN_39") (pintype "passive"))
      (node (ref "R19") (pin "2") (pinfunction "2_2") (pintype "passive"))
    )
    (net (code "50") (name "Net-(IC2-X1)") (class "Default")
      (node (ref "C16") (pin "2") (pinfunction "2_2") (pintype "passive"))
      (node (ref "IC2") (pin "14") (pinfunction "X1_14") (pintype "passive"))
      (node (ref "X1") (pin "3") (pinfunction "3_3") (pintype "passive"))
    )
    (net (code "51") (name "Net-(IC2-X2)") (class "Default")
      (node (ref "C15") (pin "2") (pinfunction "2_2") (pintype "passive"))
      (node (ref "IC2") (pin "15") (pinfunction "X2_15") (pintype "passive"))
      (node (ref "X1") (pin "1") (pinfunction "1_1") (pintype "passive"))
    )
    (net (code "52") (name "Net-(J3-G-)") (class "Default")
      (node (ref "J3") (pin "11") (pinfunction "G-_11") (pintype "passive"))
      (node (ref "R36") (pin "2") (pinfunction "2_2") (pintype "passive"))
    )
    (net (code "53") (name "Net-(J3-Pad4)") (class "Default")
      (node (ref "J3") (pin "4") (pinfunction "4_4") (pintype "passive"))
      (node (ref "R28") (pin "2") (pinfunction "2_2") (pintype "passive"))
    )
    (net (code "54") (name "Net-(J3-Pad5)") (class "Default")
      (node (ref "J3") (pin "5") (pinfunction "5_5") (pintype "passive"))
      (node (ref "R30") (pin "2") (pinfunction "2_2") (pintype "passive"))
    )
    (net (code "55") (name "Net-(J3-Pad7)") (class "Default")
      (node (ref "J3") (pin "7") (pinfunction "7_7") (pintype "passive"))
      (node (ref "R32") (pin "2") (pinfunction "2_2") (pintype "passive"))
    )
    (net (code "56") (name "Net-(J3-Pad8)") (class "Default")
      (node (ref "J3") (pin "8") (pinfunction "8_8") (pintype "passive"))
      (node (ref "R34") (pin "2") (pinfunction "2_2") (pintype "passive"))
    )
    (net (code "57") (name "Net-(J3-SHIELD)") (class "Default")
      (node (ref "C21") (pin "1") (pinfunction "1_1") (pintype "passive"))
      (node (ref "C22") (pin "2") (pinfunction "2_2") (pintype "passive"))
      (node (ref "J3") (pin "13") (pinfunction "SHIELD_13") (pintype "passive"))
    )
    (net (code "58") (name "Net-(J3-Y-)") (class "Default")
      (node (ref "J3") (pin "9") (pinfunction "Y-_9") (pintype "passive"))
      (node (ref "R35") (pin "2") (pinfunction "2_2") (pintype "passive"))
    )
    (net (code "59") (name "Net-(J4-Pad1)") (class "Default")
      (node (ref "J4") (pin "1") (pinfunction "1_1") (pintype "passive"))
      (node (ref "R35") (pin "1") (pinfunction "1_1") (pintype "passive"))
    )
    (net (code "60") (name "Net-(J5-Pad1)") (class "Default")
      (node (ref "J5") (pin "1") (pinfunction "1_1") (pintype "passive"))
      (node (ref "R36") (pin "1") (pinfunction "1_1") (pintype "passive"))
    )
    (net (code "61") (name "Net-(J6-G-)") (class "Default")
      (node (ref "J6") (pin "11") (pinfunction "G-_11") (pintype "passive"))
      (node (ref "R50") (pin "2") (pinfunction "2_2") (pintype "passive"))
    )
    (net (code "62") (name "Net-(J6-Pad4)") (class "Default")
      (node (ref "J6") (pin "4") (pinfunction "4_4") (pintype "passive"))
      (node (ref "R42") (pin "2") (pinfunction "2_2") (pintype "passive"))
    )
    (net (code "63") (name "Net-(J6-Pad5)") (class "Default")
      (node (ref "J6") (pin "5") (pinfunction "5_5") (pintype "passive"))
      (node (ref "R44") (pin "2") (pinfunction "2_2") (pintype "passive"))
    )
    (net (code "64") (name "Net-(J6-Pad7)") (class "Default")
      (node (ref "J6") (pin "7") (pinfunction "7_7") (pintype "passive"))
      (node (ref "R46") (pin "2") (pinfunction "2_2") (pintype "passive"))
    )
    (net (code "65") (name "Net-(J6-Pad8)") (class "Default")
      (node (ref "J6") (pin "8") (pinfunction "8_8") (pintype "passive"))
      (node (ref "R48") (pin "2") (pinfunction "2_2") (pintype "passive"))
    )
    (net (code "66") (name "Net-(J6-SHIELD)") (class "Default")
      (node (ref "C26") (pin "1") (pinfunction "1_1") (pintype "passive"))
      (node (ref "C27") (pin "2") (pinfunction "2_2") (pintype "passive"))
      (node (ref "J6") (pin "13") (pinfunction "SHIELD_13") (pintype "passive"))
    )
    (net (code "67") (name "Net-(J6-Y-)") (class "Default")
      (node (ref "J6") (pin "9") (pinfunction "Y-_9") (pintype "passive"))
      (node (ref "R49") (pin "2") (pinfunction "2_2") (pintype "passive"))
    )
    (net (code "68") (name "Net-(J7-Pad1)") (class "Default")
      (node (ref "J7") (pin "1") (pinfunction "1_1") (pintype "passive"))
      (node (ref "R49") (pin "1") (pinfunction "1_1") (pintype "passive"))
    )
    (net (code "69") (name "Net-(J8-Pad1)") (class "Default")
      (node (ref "J8") (pin "1") (pinfunction "1_1") (pintype "passive"))
      (node (ref "R50") (pin "1") (pinfunction "1_1") (pintype "passive"))
    )
    (net (code "70") (name "Net-(R28-Pad1)") (class "Default")
      (node (ref "R28") (pin "1") (pinfunction "1_1") (pintype "passive"))
      (node (ref "R29") (pin "2") (pinfunction "2_2") (pintype "passive"))
      (node (ref "R30") (pin "1") (pinfunction "1_1") (pintype "passive"))
    )
    (net (code "71") (name "Net-(R32-Pad1)") (class "Default")
      (node (ref "R32") (pin "1") (pinfunction "1_1") (pintype "passive"))
      (node (ref "R33") (pin "2") (pinfunction "2_2") (pintype "passive"))
      (node (ref "R34") (pin "1") (pinfunction "1_1") (pintype "passive"))
    )
    (net (code "72") (name "Net-(R42-Pad1)") (class "Default")
      (node (ref "R42") (pin "1") (pinfunction "1_1") (pintype "passive"))
      (node (ref "R43") (pin "2") (pinfunction "2_2") (pintype "passive"))
      (node (ref "R44") (pin "1") (pinfunction "1_1") (pintype "passive"))
    )
    (net (code "73") (name "Net-(R46-Pad1)") (class "Default")
      (node (ref "R46") (pin "1") (pinfunction "1_1") (pintype "passive"))
      (node (ref "R47") (pin "2") (pinfunction "2_2") (pintype "passive"))
      (node (ref "R48") (pin "1") (pinfunction "1_1") (pintype "passive"))
    )
    (net (code "74") (name "Net-(T1-RXCT)") (class "Default")
      (node (ref "R27") (pin "1") (pinfunction "1_1") (pintype "passive"))
      (node (ref "T1") (pin "10") (pinfunction "RXCT_10") (pintype "passive"))
      (node (ref "T1") (pin "15") (pinfunction "TXCT_15") (pintype "passive"))
    )
    (net (code "75") (name "Net-(T2-RXCT)") (class "Default")
      (node (ref "R41") (pin "1") (pinfunction "1_1") (pintype "passive"))
      (node (ref "T2") (pin "10") (pinfunction "RXCT_10") (pintype "passive"))
      (node (ref "T2") (pin "15") (pinfunction "TXCT_15") (pintype "passive"))
    )
    (net (code "76") (name "unconnected-(IC2-SCOL3-Pad33)") (class "Default")
      (node (ref "IC2") (pin "33") (pinfunction "SCOL3_33") (pintype "passive"))
    )
    (net (code "77") (name "unconnected-(IC2-SCRS3-Pad34)") (class "Default")
      (node (ref "IC2") (pin "34") (pinfunction "SCRS3_34") (pintype "passive"))
    )
    (net (code "78") (name "unconnected-(IC2-SMRXC3-Pad30)") (class "Default")
      (node (ref "IC2") (pin "30") (pinfunction "SMRXC3_30") (pintype "passive"))
    )
    (net (code "79") (name "unconnected-(IC2-SMTXD32-Pad18)") (class "Default")
      (node (ref "IC2") (pin "18") (pinfunction "SMTXD32_18") (pintype "passive"))
    )
    (net (code "80") (name "unconnected-(IC2-SMTXER3{slash}MII_LINK_3-Pad24)") (class "Default")
      (node (ref "IC2") (pin "24") (pinfunction "SMTXER3/MII_LINK_3_24") (pintype "passive"))
    )
  )
)
